# WaterbedSlave.net
KiCad netlist of a schematic drawn in EAGLE
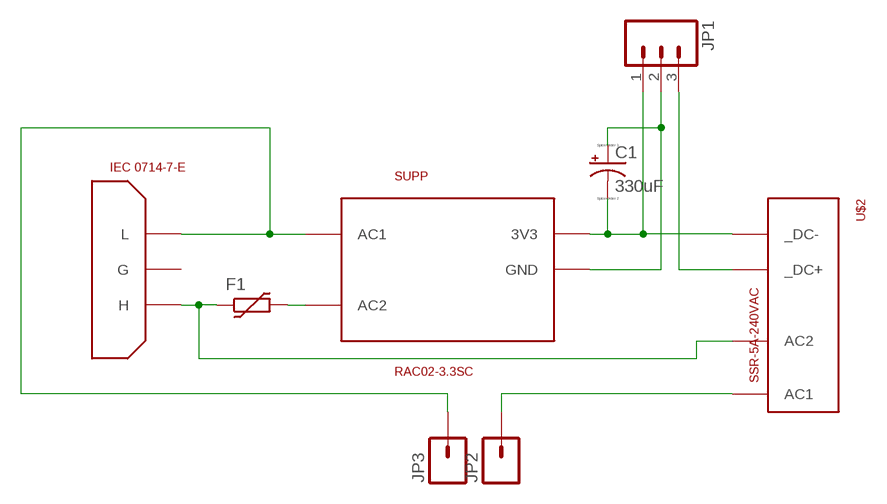
[diagram p0: schematic, sheet 1]

(export (version "E")
  (design (tool "Eeschema 10.0.6"))
  (components
    (comp (ref "C1")
      (value "330uF")
      (footprint "eagle-import:TT5D9")
      (libsource (lib "eagle-import") (part "CPOL-USTT5D9"))
    )
    (comp (ref "F1")
      (value "FUSE_PTC-1812")
      (footprint "eagle-import:PTC1812L")
      (libsource (lib "eagle-import") (part "FUSE_PTC-1812"))
    )
    (comp (ref "JP1")
      (value "M03POLAR_LOCK")
      (footprint "eagle-import:MOLEX-1X3_LOCK")
      (libsource (lib "eagle-import") (part "M03POLAR_LOCK"))
    )
    (comp (ref "JP2")
      (value "M01PTH_2MM")
      (footprint "eagle-import:1X01_2MM")
      (libsource (lib "eagle-import") (part "M01PTH_2MM"))
    )
    (comp (ref "JP3")
      (value "M01PTH_2MM")
      (footprint "eagle-import:1X01_2MM")
      (libsource (lib "eagle-import") (part "M01PTH_2MM"))
    )
    (comp (ref "SUPP")
      (value "RAC02-3.3SC")
      (footprint "eagle-import:RAC02-3.3SC")
      (libsource (lib "eagle-import") (part "RAC02-3.3SC"))
    )
    (comp (ref "U$2")
      (value "SSR-5A-240VAC")
      (footprint "eagle-import:SIP-4")
      (libsource (lib "eagle-import") (part "SSR-5A-240VAC"))
    )
    (comp (ref "U$3")
      (value "IEC 0714-7-E")
      (footprint "eagle-import:IEC")
      (libsource (lib "eagle-import") (part "IEC"))
    )
  )
  (nets
    (net (code "1") (name "Net-(C1-Pad+)") (class "Default")
      (node (ref "C1") (pin "+") (pinfunction "+_+") (pintype "passive"))
      (node (ref "JP1") (pin "2") (pinfunction "2_2") (pintype "passive"))
      (node (ref "SUPP") (pin "GND") (pinfunction "GND_GND") (pintype "bidirectional"))
    )
    (net (code "2") (name "Net-(F1-Pad2)") (class "Default")
      (node (ref "F1") (pin "2") (pinfunction "2_2") (pintype "passive"))
      (node (ref "SUPP") (pin "AC2") (pinfunction "AC2_AC2") (pintype "bidirectional"))
    )
    (net (code "3") (name "Net-(JP3-Pad1)") (class "Default")
      (node (ref "JP3") (pin "1") (pinfunction "1_1") (pintype "passive"))
      (node (ref "SUPP") (pin "AC1") (pinfunction "AC1_AC1") (pintype "bidirectional"))
      (node (ref "U$3") (pin "L") (pinfunction "L_L") (pintype "power_in"))
    )
    (net (code "4") (name "Net-(U$2-AC1)") (class "Default")
      (node (ref "JP2") (pin "1") (pinfunction "1_1") (pintype "passive"))
      (node (ref "U$2") (pin "P$4") (pinfunction "AC1_P$4") (pintype "bidirectional"))
    )
    (net (code "5") (name "Net-(U$2-AC2)") (class "Default")
      (node (ref "F1") (pin "1") (pinfunction "1_1") (pintype "passive"))
      (node (ref "U$2") (pin "P$3") (pinfunction "AC2_P$3") (pintype "bidirectional"))
      (node (ref "U$3") (pin "H") (pinfunction "H_H") (pintype "power_in"))
    )
    (net (code "6") (name "Net-(U$2-_DC+)") (class "Default")
      (node (ref "JP1") (pin "3") (pinfunction "3_3") (pintype "passive"))
      (node (ref "U$2") (pin "P$2") (pinfunction "_DC+_P$2") (pintype "bidirectional"))
    )
    (net (code "7") (name "Net-(U$2-_DC-)") (class "Default")
      (node (ref "C1") (pin "-") (pinfunction "-_-") (pintype "passive"))
      (node (ref "JP1") (pin "1") (pinfunction "1_1") (pintype "passive"))
      (node (ref "SUPP") (pin "3V3") (pinfunction "3V3_3V3") (pintype "bidirectional"))
      (node (ref "U$2") (pin "P$1") (pinfunction "_DC-_P$1") (pintype "bidirectional"))
    )
    (net (code "8") (name "unconnected-(U$3-PadG)") (class "Default")
      (node (ref "U$3") (pin "G") (pinfunction "G_G") (pintype "passive"))
    )
  )
)
